# Li_power.net
KiCad netlist of a schematic drawn in Altium Designer
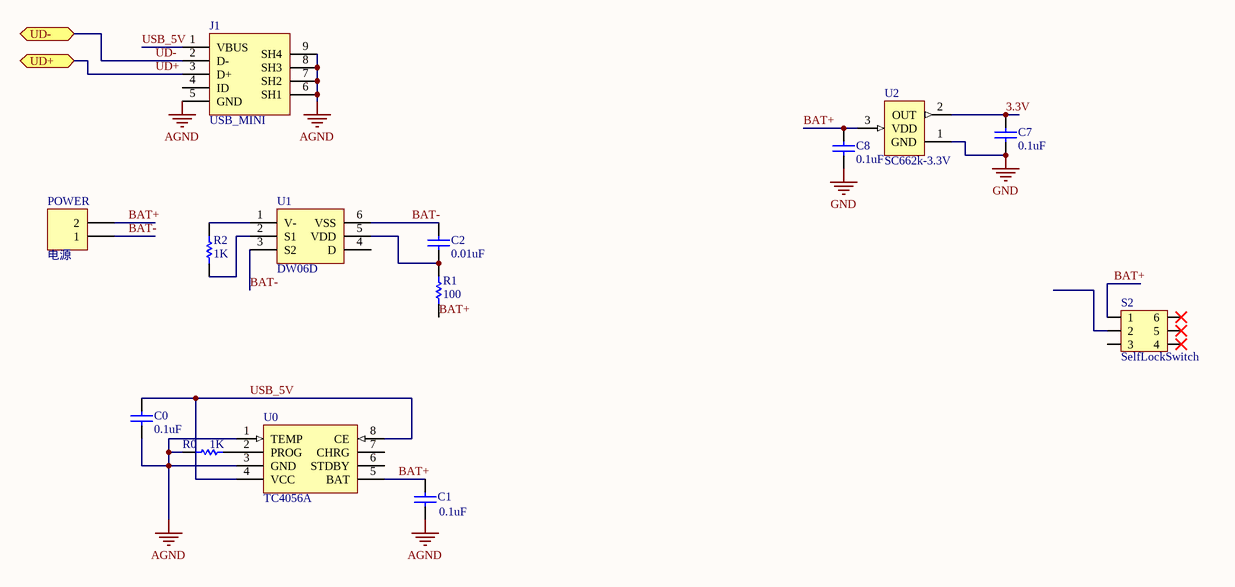
[diagram p0: Li_power.SchDoc]

(export (version "E")
  (design (tool "Eeschema 10.0.6"))
  (components
    (comp (ref "C0")
      (value "0.1uF")
      (footprint "RAD-0.3")
      (description "Capacitor")
      (fields (field (name "Comment") "Cap") (field (name "PUBLISHER") "Altium Limited"))
      (libsource (lib "Miscellaneous Devices") (part "Cap"))
    )
    (comp (ref "C1")
      (value "0.1uF")
      (footprint "RAD-0.3")
      (description "Capacitor")
      (fields (field (name "Comment") "Cap") (field (name "PUBLISHER") "Altium Limited"))
      (libsource (lib "Miscellaneous Devices") (part "Cap"))
    )
    (comp (ref "C2")
      (value "0.01uF")
      (footprint "RAD-0.3")
      (description "Capacitor")
      (fields (field (name "Comment") "Cap") (field (name "PUBLISHER") "Altium Limited"))
      (libsource (lib "Miscellaneous Devices") (part "Cap"))
    )
    (comp (ref "C7")
      (value "0.1uF")
      (footprint "RAD-0.3")
      (description "Capacitor")
      (fields (field (name "Comment") "Cap") (field (name "PUBLISHER") "Altium Limited"))
      (libsource (lib "Miscellaneous Devices") (part "Cap"))
    )
    (comp (ref "C8")
      (value "0.1uF")
      (footprint "RAD-0.3")
      (description "Capacitor")
      (fields (field (name "Comment") "Cap") (field (name "PUBLISHER") "Altium Limited"))
      (libsource (lib "Miscellaneous Devices") (part "Cap"))
    )
    (comp (ref "J1")
      (value "USB_MINI")
      (footprint "MICRO_USB")
      (libsource (lib "YYB-Schlib1") (part "USB_MINI"))
    )
    (comp (ref "POWER")
      (value "电源")
      (footprint "HDR1X2")
      (description "Header, 2-Pin")
      (fields (field (name "PUBLISHER") "Altium Limited"))
      (libsource (lib "Miscellaneous Connectors") (part "Header 2"))
    )
    (comp (ref "R0")
      (value "1K")
      (footprint "AXIAL-0.3")
      (description "Resistor")
      (fields (field (name "Comment") "Res1") (field (name "PUBLISHER") "Altium Limited"))
      (libsource (lib "Miscellaneous Devices") (part "Res1"))
    )
    (comp (ref "R1")
      (value "100")
      (footprint "AXIAL-0.3")
      (description "Resistor")
      (fields (field (name "Comment") "Res1") (field (name "PUBLISHER") "Altium Limited"))
      (libsource (lib "Miscellaneous Devices") (part "Res1"))
    )
    (comp (ref "R2")
      (value "1K")
      (footprint "AXIAL-0.3")
      (description "Resistor")
      (fields (field (name "Comment") "Res1") (field (name "PUBLISHER") "Altium Limited"))
      (libsource (lib "Miscellaneous Devices") (part "Res1"))
    )
    (comp (ref "S2")
      (value "SelfLockSwitch")
      (footprint "KEY_ZS_5.8*5.8")
      (libsource (lib "Schlib") (part "SelfLockSwitch"))
    )
    (comp (ref "U0")
      (value "TC4056A")
      (footprint "SOP-8")
      (description "锂电池充电")
      (libsource (lib "aistlab") (part "TC4056A"))
    )
    (comp (ref "U1") (value "DW06D") (description "锂电池保护芯片") (libsource (lib "aistlab") (part "DW06D")))
    (comp (ref "U2") (value "SC662k-3.3V") (libsource (lib "YYB-Schlib1") (part "SC662k-3.3V")))
  )
  (nets
    (net (code "1") (name "/3.3V") (class "Default")
      (node (ref "C7") (pin "2") (pinfunction "2_2") (pintype "passive"))
      (node (ref "U2") (pin "2") (pinfunction "OUT_2") (pintype "output"))
    )
    (net (code "2") (name "/BAT+") (class "Default")
      (node (ref "C1") (pin "2") (pinfunction "2_2") (pintype "passive"))
      (node (ref "C8") (pin "1") (pinfunction "1_1") (pintype "passive"))
      (node (ref "POWER") (pin "2") (pinfunction "2_2") (pintype "passive"))
      (node (ref "R1") (pin "1") (pinfunction "1_1") (pintype "passive"))
      (node (ref "S2") (pin "1") (pinfunction "1_1") (pintype "passive"))
      (node (ref "U0") (pin "5") (pinfunction "BAT_5") (pintype "power_in"))
      (node (ref "U2") (pin "3") (pinfunction "VDD_3") (pintype "input"))
    )
    (net (code "3") (name "/BAT-") (class "Default")
      (node (ref "C2") (pin "2") (pinfunction "2_2") (pintype "passive"))
      (node (ref "POWER") (pin "1") (pinfunction "1_1") (pintype "passive"))
      (node (ref "U1") (pin "3") (pinfunction "S2_3") (pintype "power_in"))
      (node (ref "U1") (pin "6") (pinfunction "VSS_6") (pintype "power_in"))
    )
    (net (code "4") (name "/UD+") (class "Default")
      (node (ref "J1") (pin "3") (pinfunction "D+_3") (pintype "passive"))
    )
    (net (code "5") (name "/UD-") (class "Default")
      (node (ref "J1") (pin "2") (pinfunction "D-_2") (pintype "passive"))
    )
    (net (code "6") (name "/USB_5V") (class "Default")
      (node (ref "C0") (pin "2") (pinfunction "2_2") (pintype "passive"))
      (node (ref "J1") (pin "1") (pinfunction "VBUS_1") (pintype "passive"))
      (node (ref "U0") (pin "4") (pinfunction "VCC_4") (pintype "power_in"))
      (node (ref "U0") (pin "8") (pinfunction "CE_8") (pintype "input"))
    )
    (net (code "7") (name "AGND") (class "Default")
      (node (ref "C0") (pin "1") (pinfunction "1_1") (pintype "passive"))
      (node (ref "C1") (pin "1") (pinfunction "1_1") (pintype "passive"))
      (node (ref "J1") (pin "5") (pinfunction "GND_5") (pintype "passive"))
      (node (ref "J1") (pin "6") (pinfunction "SH1_6") (pintype "passive"))
      (node (ref "J1") (pin "7") (pinfunction "SH2_7") (pintype "passive"))
      (node (ref "J1") (pin "8") (pinfunction "SH3_8") (pintype "passive"))
      (node (ref "J1") (pin "9") (pinfunction "SH4_9") (pintype "passive"))
      (node (ref "R0") (pin "1") (pinfunction "1_1") (pintype "passive"))
      (node (ref "U0") (pin "1") (pinfunction "TEMP_1") (pintype "input"))
      (node (ref "U0") (pin "3") (pinfunction "GND_3") (pintype "power_in"))
    )
    (net (code "8") (name "GND") (class "Default")
      (node (ref "C7") (pin "1") (pinfunction "1_1") (pintype "passive"))
      (node (ref "C8") (pin "2") (pinfunction "2_2") (pintype "passive"))
      (node (ref "U2") (pin "1") (pinfunction "GND_1") (pintype "power_in"))
    )
    (net (code "9") (name "Net-(U0-PROG)") (class "Default")
      (node (ref "R0") (pin "2") (pinfunction "2_2") (pintype "passive"))
      (node (ref "U0") (pin "2") (pinfunction "PROG_2") (pintype "passive"))
    )
    (net (code "10") (name "Net-(U1-S1)") (class "Default")
      (node (ref "R2") (pin "1") (pinfunction "1_1") (pintype "passive"))
      (node (ref "U1") (pin "2") (pinfunction "S1_2") (pintype "power_in"))
    )
    (net (code "11") (name "Net-(U1-V-)") (class "Default")
      (node (ref "R2") (pin "2") (pinfunction "2_2") (pintype "passive"))
      (node (ref "U1") (pin "1") (pinfunction "V-_1") (pintype "power_in"))
    )
    (net (code "12") (name "Net-(U1-VDD)") (class "Default")
      (node (ref "C2") (pin "1") (pinfunction "1_1") (pintype "passive"))
      (node (ref "R1") (pin "2") (pinfunction "2_2") (pintype "passive"))
      (node (ref "U1") (pin "5") (pinfunction "VDD_5") (pintype "power_in"))
    )
    (net (code "13") (name "unconnected-(J1-ID-Pad4)") (class "Default")
      (node (ref "J1") (pin "4") (pinfunction "ID_4") (pintype "passive"))
    )
    (net (code "14") (name "unconnected-(S2-Pad2)") (class "Default")
      (node (ref "S2") (pin "2") (pinfunction "2_2") (pintype "passive"))
    )
    (net (code "15") (name "unconnected-(S2-Pad3)") (class "Default")
      (node (ref "S2") (pin "3") (pinfunction "3_3") (pintype "passive"))
    )
    (net (code "16") (name "unconnected-(S2-Pad4)") (class "Default")
      (node (ref "S2") (pin "4") (pinfunction "4_4") (pintype "passive+no_connect"))
    )
    (net (code "17") (name "unconnected-(S2-Pad5)") (class "Default")
      (node (ref "S2") (pin "5") (pinfunction "5_5") (pintype "passive+no_connect"))
    )
    (net (code "18") (name "unconnected-(S2-Pad6)") (class "Default")
      (node (ref "S2") (pin "6") (pinfunction "6_6") (pintype "passive+no_connect"))
    )
    (net (code "19") (name "unconnected-(U0-CHRG-Pad7)") (class "Default")
      (node (ref "U0") (pin "7") (pinfunction "CHRG_7") (pintype "open_collector"))
    )
    (net (code "20") (name "unconnected-(U0-STDBY-Pad6)") (class "Default")
      (node (ref "U0") (pin "6") (pinfunction "STDBY_6") (pintype "open_collector"))
    )
    (net (code "21") (name "unconnected-(U1-D-Pad4)") (class "Default")
      (node (ref "U1") (pin "4") (pinfunction "D_4") (pintype "power_in"))
    )
  )
)
